# SH3_-_USB.net
KiCad netlist of a schematic drawn in Altium Designer
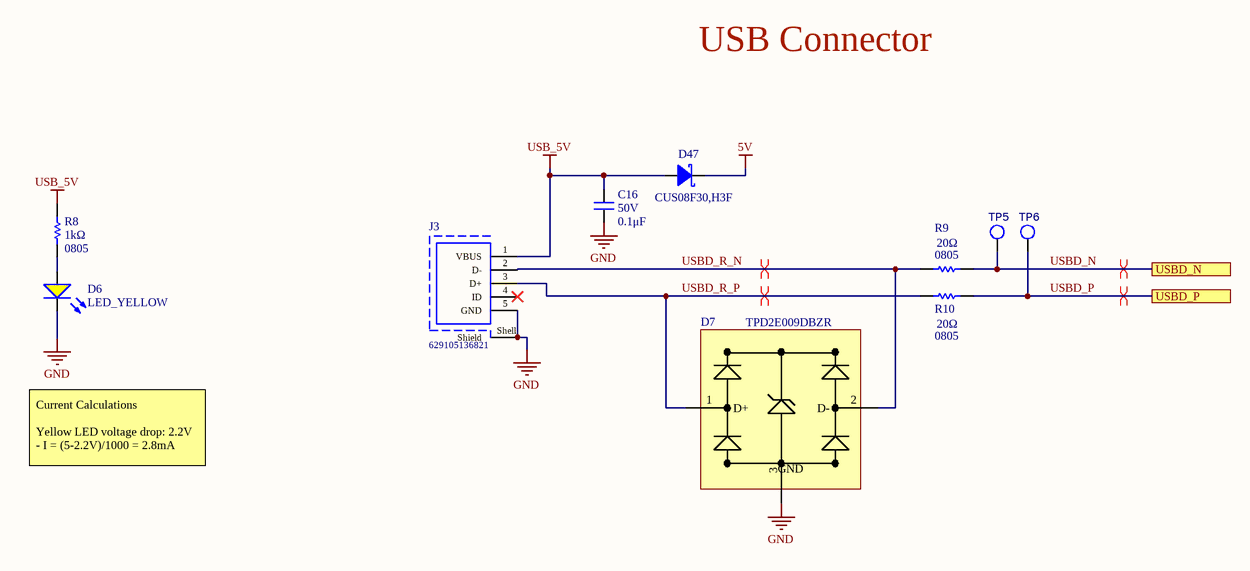
[diagram p0: SH3 - USB.SchDoc]

(export (version "E")
  (design (tool "Eeschema 10.0.6"))
  (components
    (comp (ref "C16")
      (value "0.1μF")
      (footprint "CAP2012")
      (description "CAP CER 0.1UF 50V X7R 0805")
      (fields
        (field (name "VOLTAGE RATING") "50V")
        (field (name "LCSC PART #") "C49678")
        (field (name "Comment") "CAP_0.1uF_50V_0805")
      )
      (libsource (lib "UWRT_Schematic_Library_2020") (part "CAP_0.1uF_50V_0805"))
    )
    (comp (ref "D6")
      (value "LED_YELLOW")
      (footprint "LED_0805_YELLOW")
      (description "LED YELLOW DIFFUSED 0805 SMD")
      (libsource (lib "UWRT_Schematic_Library_2020") (part "LED_YELLOW"))
    )
    (comp (ref "D7")
      (value "TVS_DIODE_USB_5.5V")
      (footprint "SOT23-3")
      (description "TVS DIODE 5.5V 8V SOT23-3")
      (fields (field (name "MANUFACTURER PART NUMBER 1") "TPD2E009DBZR"))
      (libsource (lib "UWRT_Schematic_Library_2020") (part "TVS_DIODE_USB_5.5V"))
    )
    (comp (ref "D47")
      (value "DIO_SCHOTTKY_30V_800mA")
      (footprint "SOD-323_UNIDIR")
      (description "DIODE SCHOTTKY 30V 800MA USC")
      (fields (field (name "MANUFACTURER PART NUMBER 1") "CUS08F30,H3F"))
      (libsource (lib "UWRT_Schematic_Library_2020") (part "DIO_SCHOTTKY_30V_800mA"))
    )
    (comp (ref "J3")
      (value "629105136821")
      (footprint "629105136821")
      (description "Micro USB 2.0 Type B Receptacle WR-COM, Horizontal, SMT, with Pads and Pegs")
      (fields (field (name "MANUFACTURER") "Wurth Elektronik") (field (name "PUBLISHER") "WurthElektronik"))
      (libsource (lib "Altium Content Vault") (part "WE-USB-5-1SHLD"))
    )
    (comp (ref "R8")
      (value "RES_1kΩ_0805_1%")
      (footprint "RESC0805")
      (description "RES 1K OHM 1% 1/8W 0805")
      (fields
        (field (name "LCSC PART #") "C17513")
        (field (name "PACKAGE/FOOTPRINT") "0805")
        (field (name "PARAMETER 1") "1kΩ")
      )
      (libsource (lib "UWRT_Schematic_Library_2020") (part "RES_1kΩ_0805_1%"))
    )
    (comp (ref "R9")
      (value "20Ω")
      (footprint "RESC0805")
      (description "RES 20 OHM 1% 1/8W 0805")
      (fields
        (field (name "LCSC PART #") "C17581")
        (field (name "PACKAGE/FOOTPRINT") "0805")
        (field (name "Comment") "RES_20Ω_0805_1%")
      )
      (libsource (lib "UWRT_Schematic_Library_2020") (part "RES_20Ω_0805_1%"))
    )
    (comp (ref "R10")
      (value "20Ω")
      (footprint "RESC0805")
      (description "RES 20 OHM 1% 1/8W 0805")
      (fields
        (field (name "LCSC PART #") "C17581")
        (field (name "PACKAGE/FOOTPRINT") "0805")
        (field (name "Comment") "RES_20Ω_0805_1%")
      )
      (libsource (lib "UWRT_Schematic_Library_2020") (part "RES_20Ω_0805_1%"))
    )
    (comp (ref "TP5")
      (value "TESTPOINT_LOOP")
      (footprint "TESTPOINT_LOOP")
      (description "TESTPOINT THRUHOLE")
      (libsource (lib "UWRT_Schematic_Library_2020") (part "TESTPOINT_LOOP"))
    )
    (comp (ref "TP6")
      (value "TESTPOINT_LOOP")
      (footprint "TESTPOINT_LOOP")
      (description "TESTPOINT THRUHOLE")
      (libsource (lib "UWRT_Schematic_Library_2020") (part "TESTPOINT_LOOP"))
    )
  )
  (nets
    (net (code "1") (name "/USBD_N") (class "Default")
      (node (ref "R9") (pin "2") (pinfunction "2_2") (pintype "passive"))
      (node (ref "TP5") (pin "1") (pintype "passive"))
    )
    (net (code "2") (name "/USBD_P") (class "Default")
      (node (ref "R10") (pin "2") (pinfunction "2_2") (pintype "passive"))
      (node (ref "TP6") (pin "1") (pintype "passive"))
    )
    (net (code "3") (name "/USBD_R_N") (class "Default")
      (node (ref "D7") (pin "2") (pinfunction "D-_2") (pintype "passive"))
      (node (ref "J3") (pin "2") (pinfunction "D-_2") (pintype "passive"))
      (node (ref "R9") (pin "1") (pinfunction "1_1") (pintype "passive"))
    )
    (net (code "4") (name "/USBD_R_P") (class "Default")
      (node (ref "D7") (pin "1") (pinfunction "D+_1") (pintype "passive"))
      (node (ref "J3") (pin "3") (pinfunction "D+_3") (pintype "passive"))
      (node (ref "R10") (pin "1") (pinfunction "1_1") (pintype "passive"))
    )
    (net (code "5") (name "5V") (class "Default")
      (node (ref "D47") (pin "2") (pinfunction "Cathode_2") (pintype "passive"))
    )
    (net (code "6") (name "GND") (class "Default")
      (node (ref "C16") (pin "2") (pinfunction "2_2") (pintype "passive"))
      (node (ref "D6") (pin "2") (pinfunction "K_2") (pintype "passive"))
      (node (ref "D7") (pin "3") (pinfunction "GND_3") (pintype "passive"))
      (node (ref "J3") (pin "5") (pinfunction "GND_5") (pintype "passive"))
      (node (ref "J3") (pin "Shell") (pinfunction "Shield_Shell") (pintype "passive"))
    )
    (net (code "7") (name "Net-(D6-A)") (class "Default")
      (node (ref "D6") (pin "1") (pinfunction "A_1") (pintype "passive"))
      (node (ref "R8") (pin "1") (pinfunction "1_1") (pintype "passive"))
    )
    (net (code "8") (name "USB_5V") (class "Default")
      (node (ref "C16") (pin "1") (pinfunction "1_1") (pintype "passive"))
      (node (ref "D47") (pin "1") (pinfunction "Anode_1") (pintype "passive"))
      (node (ref "J3") (pin "1") (pinfunction "VBUS_1") (pintype "passive"))
      (node (ref "R8") (pin "2") (pinfunction "2_2") (pintype "passive"))
    )
    (net (code "9") (name "unconnected-(J3-ID-Pad4)") (class "Default")
      (node (ref "J3") (pin "4") (pinfunction "ID_4") (pintype "passive+no_connect"))
    )
  )
)
